# evalboard_v2_9.net
KiCad netlist of a schematic drawn in EAGLE
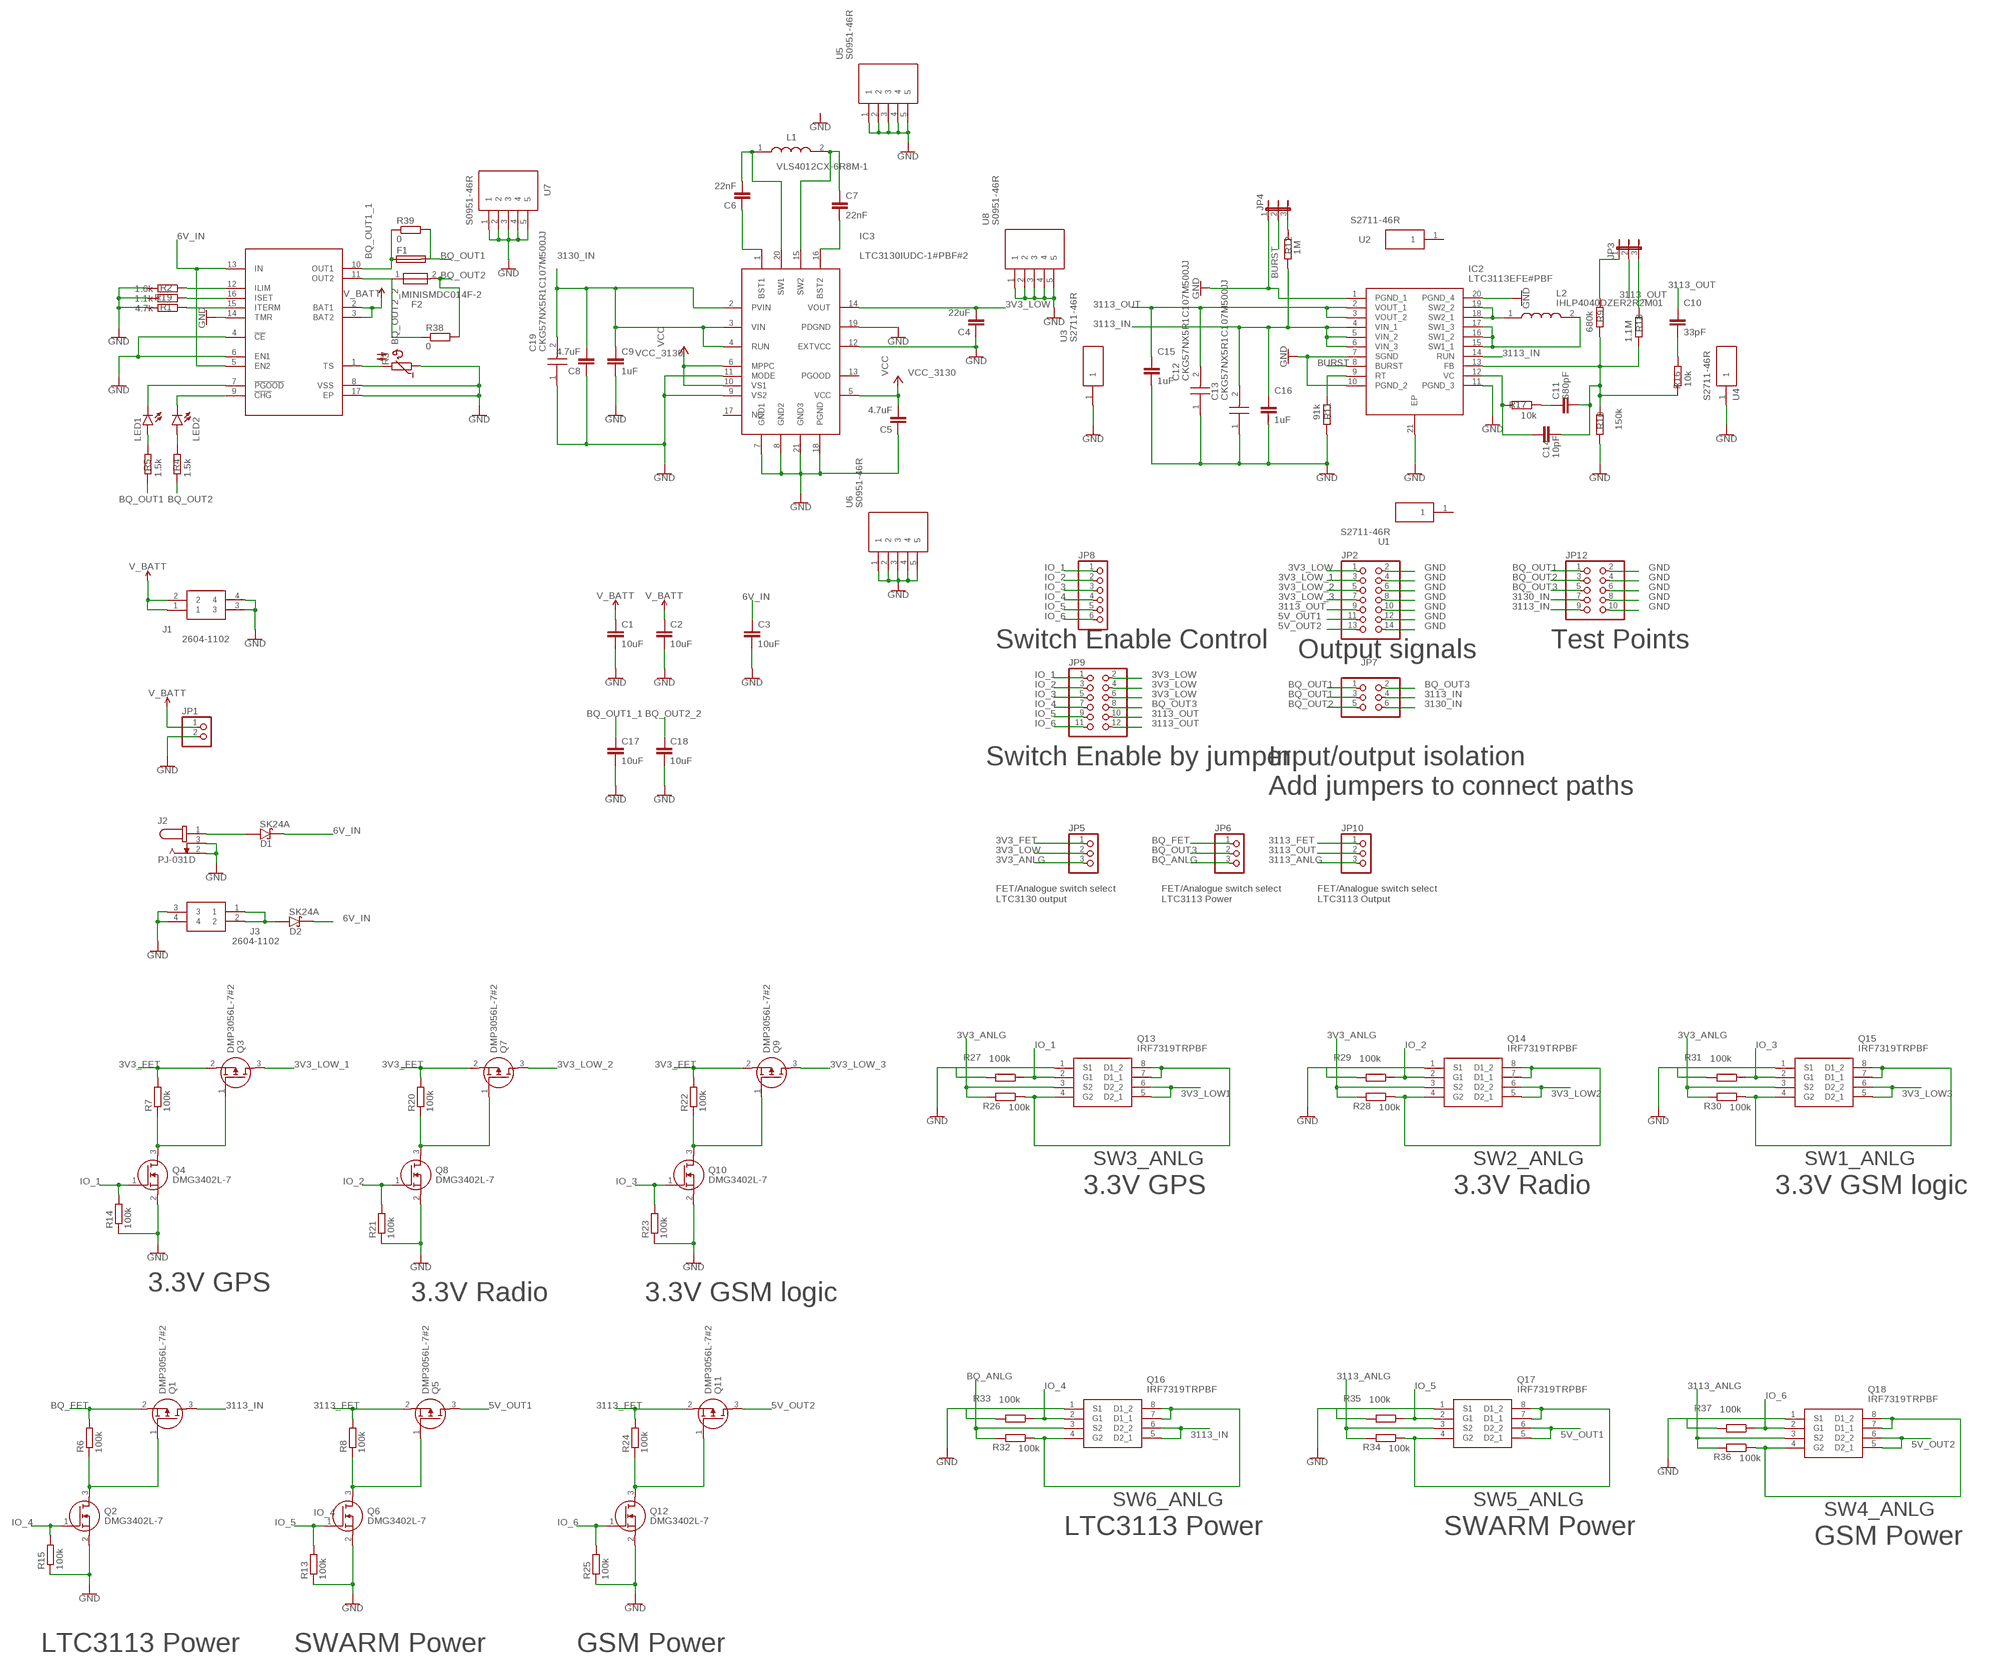
[diagram p0: schematic, sheet 1]

(export (version "E")
  (design (tool "Eeschema 10.0.6"))
  (components
    (comp (ref "C1")
      (value "10uF")
      (footprint "eagle-import:C1210")
      (libsource (lib "eagle-import") (part "C-EUC1210"))
    )
    (comp (ref "C2")
      (value "10uF")
      (footprint "eagle-import:C1210")
      (libsource (lib "eagle-import") (part "C-EUC1210"))
    )
    (comp (ref "C3")
      (value "10uF")
      (footprint "eagle-import:C1210")
      (libsource (lib "eagle-import") (part "C-EUC1210"))
    )
    (comp (ref "C4")
      (value "22uF")
      (footprint "eagle-import:C1210")
      (libsource (lib "eagle-import") (part "C-EUC1210"))
    )
    (comp (ref "C5")
      (value "4.7uF")
      (footprint "eagle-import:C1210")
      (libsource (lib "eagle-import") (part "C-EUC1210"))
    )
    (comp (ref "C6")
      (value "22nF")
      (footprint "eagle-import:C0603")
      (libsource (lib "eagle-import") (part "C-EUC0603"))
    )
    (comp (ref "C7")
      (value "22nF")
      (footprint "eagle-import:C0603")
      (libsource (lib "eagle-import") (part "C-EUC0603"))
    )
    (comp (ref "C8")
      (value "4.7uF")
      (footprint "eagle-import:C1210")
      (libsource (lib "eagle-import") (part "C-EUC1210"))
    )
    (comp (ref "C9")
      (value "1uF")
      (footprint "eagle-import:C0603")
      (libsource (lib "eagle-import") (part "C-EUC0603"))
    )
    (comp (ref "C10")
      (value "33pF")
      (footprint "eagle-import:C0603")
      (libsource (lib "eagle-import") (part "C-EUC0603"))
    )
    (comp (ref "C11")
      (value "680pF")
      (footprint "eagle-import:C0603")
      (libsource (lib "eagle-import") (part "C-EUC0603"))
    )
    (comp (ref "C12")
      (value "CKG57NX5R1C107M500JJ")
      (footprint "eagle-import:CAPC6050X550N")
      (fields (field (name "MOUSER_PART_NUMBER") "810-CKG57NX5R1C107MJ"))
      (libsource (lib "eagle-import") (part "CKG57NX5R1C107M500JJ"))
    )
    (comp (ref "C13")
      (value "CKG57NX5R1C107M500JJ")
      (footprint "eagle-import:CAPC6050X550N")
      (fields (field (name "MOUSER_PART_NUMBER") "810-CKG57NX5R1C107MJ"))
      (libsource (lib "eagle-import") (part "CKG57NX5R1C107M500JJ"))
    )
    (comp (ref "C14")
      (value "10pF")
      (footprint "eagle-import:C0603")
      (libsource (lib "eagle-import") (part "C-EUC0603"))
    )
    (comp (ref "C15")
      (value "1uF")
      (footprint "eagle-import:C0603")
      (libsource (lib "eagle-import") (part "C-EUC0603"))
    )
    (comp (ref "C16")
      (value "1uF")
      (footprint "eagle-import:C0603")
      (libsource (lib "eagle-import") (part "C-EUC0603"))
    )
    (comp (ref "C17")
      (value "10uF")
      (footprint "eagle-import:C1210")
      (libsource (lib "eagle-import") (part "C-EUC1210"))
    )
    (comp (ref "C18")
      (value "10uF")
      (footprint "eagle-import:C1210")
      (libsource (lib "eagle-import") (part "C-EUC1210"))
    )
    (comp (ref "C19")
      (value "CKG57NX5R1C107M500JJ")
      (footprint "eagle-import:CAPC6050X550N")
      (fields (field (name "MOUSER_PART_NUMBER") "810-CKG57NX5R1C107MJ"))
      (libsource (lib "eagle-import") (part "CKG57NX5R1C107M500JJ"))
    )
    (comp (ref "D1")
      (value "SK24A")
      (footprint "eagle-import:DIOM4325X250N")
      (fields (field (name "DIGI-KEY_PART_NUMBER") "1655-SK24ATR-ND") (field (name "MF") "SMC Diode"))
      (libsource (lib "eagle-import") (part "SK24A"))
    )
    (comp (ref "D2")
      (value "SK24A")
      (footprint "eagle-import:DIOM4325X250N")
      (fields (field (name "DIGI-KEY_PART_NUMBER") "1655-SK24ATR-ND") (field (name "MF") "SMC Diode"))
      (libsource (lib "eagle-import") (part "SK24A"))
    )
    (comp (ref "F1")
      (value "MF-USHT150KX-2SMD")
      (footprint "eagle-import:1210")
      (libsource (lib "eagle-import") (part "MF-USHT150KX-2SMD"))
    )
    (comp (ref "F2")
      (value "MINISMDC014F-2")
      (footprint "eagle-import:FUSSC455X324X89-2N")
      (fields (field (name "MF") "Littelfuse Inc."))
      (libsource (lib "eagle-import") (part "MINISMDC014F-2"))
    )
    (comp (ref "IC1")
      (value "BQ24074")
      (footprint "eagle-import:QFN50P300X300X100-17N")
      (libsource (lib "eagle-import") (part "BQ24074"))
    )
    (comp (ref "IC2")
      (value "LTC3113EFE#PBF")
      (footprint "eagle-import:SOP65P640X120-21N")
      (fields (field (name "MOUSER_PART_NUMBER") "584-LTC3113EFE#PBF"))
      (libsource (lib "eagle-import") (part "LTC3113EFE#PBF"))
    )
    (comp (ref "IC3")
      (value "LTC3130IUDC-1#PBF#2")
      (footprint "eagle-import:QFN50P300X400X80-21N")
      (fields (field (name "MANUFACTURER_PART_NUMBER") "LTC3130IUDC-1#PBF"))
      (libsource (lib "eagle-import") (part "LTC3130IUDC-1#PBF#2"))
    )
    (comp (ref "J1")
      (value "2604-1102")
      (footprint "eagle-import:26041102")
      (libsource (lib "eagle-import") (part "2604-1102"))
    )
    (comp (ref "J2")
      (value "PJ-031D")
      (footprint "eagle-import:CUI_PJ-031D")
      (fields (field (name "MF") "CUI Devices"))
      (libsource (lib "eagle-import") (part "PJ-031D"))
    )
    (comp (ref "J3")
      (value "2604-1102")
      (footprint "eagle-import:26041102")
      (libsource (lib "eagle-import") (part "2604-1102"))
    )
    (comp (ref "JP1")
      (value "PINHD-1X2")
      (footprint "eagle-import:1X02")
      (libsource (lib "eagle-import") (part "PINHD-1X2"))
    )
    (comp (ref "JP2")
      (value "PINHD-2X7")
      (footprint "eagle-import:2X07")
      (libsource (lib "eagle-import") (part "PINHD-2X7"))
    )
    (comp (ref "JP3")
      (value "JP2E")
      (footprint "eagle-import:JP2")
      (libsource (lib "eagle-import") (part "JP2E"))
    )
    (comp (ref "JP4")
      (value "JP2E")
      (footprint "eagle-import:JP2")
      (libsource (lib "eagle-import") (part "JP2E"))
    )
    (comp (ref "JP5")
      (value "PINHD-1X3")
      (footprint "eagle-import:1X03")
      (libsource (lib "eagle-import") (part "PINHD-1X3"))
    )
    (comp (ref "JP6")
      (value "PINHD-1X3")
      (footprint "eagle-import:1X03")
      (libsource (lib "eagle-import") (part "PINHD-1X3"))
    )
    (comp (ref "JP7")
      (value "PINHD-2X3")
      (footprint "eagle-import:2X03")
      (libsource (lib "eagle-import") (part "PINHD-2X3"))
    )
    (comp (ref "JP8")
      (value "PINHD-1X6")
      (footprint "eagle-import:1X06")
      (libsource (lib "eagle-import") (part "PINHD-1X6"))
    )
    (comp (ref "JP9")
      (value "PINHD-2X6")
      (footprint "eagle-import:2X06")
      (libsource (lib "eagle-import") (part "PINHD-2X6"))
    )
    (comp (ref "JP10")
      (value "PINHD-1X3")
      (footprint "eagle-import:1X03")
      (libsource (lib "eagle-import") (part "PINHD-1X3"))
    )
    (comp (ref "JP12")
      (value "PINHD-2X5")
      (footprint "eagle-import:2X05")
      (libsource (lib "eagle-import") (part "PINHD-2X5"))
    )
    (comp (ref "L1")
      (value "VLS4012CX-6R8M-1")
      (footprint "eagle-import:VLS4012")
      (libsource (lib "eagle-import") (part "VLS4012CX-6R8M-1"))
    )
    (comp (ref "L2")
      (value "IHLP4040DZER2R2M01")
      (footprint "eagle-import:INDPM108102X400N")
      (fields (field (name "MOUSER_PART_NUMBER") "70-IHLP4040DZER2R2M0"))
      (libsource (lib "eagle-import") (part "IHLP4040DZER2R2M01"))
    )
    (comp (ref "LED1")
      (value "LEDCHIP-LED0603")
      (footprint "eagle-import:CHIP-LED0603")
      (libsource (lib "eagle-import") (part "LEDCHIP-LED0603"))
    )
    (comp (ref "LED2")
      (value "LEDCHIP-LED0603")
      (footprint "eagle-import:CHIP-LED0603")
      (libsource (lib "eagle-import") (part "LEDCHIP-LED0603"))
    )
    (comp (ref "Q1")
      (value "DMP3056L-7#2")
      (footprint "eagle-import:SOT96P240X100-3N")
      (fields
        (field (name "ARROW_PART_NUMBER") "DMP3056L-7")
        (field (name "MOUSER_PART_NUMBER") "621-DMP3056L-7")
      )
      (libsource (lib "eagle-import") (part "DMP3056L-7#2"))
    )
    (comp (ref "Q2")
      (value "DMG3402L-7")
      (footprint "eagle-import:SOT96P240X110-3N")
      (fields (field (name "MOUSER_PART_NUMBER") "621-DMG3402L-7"))
      (libsource (lib "eagle-import") (part "DMG3402L-7"))
    )
    (comp (ref "Q3")
      (value "DMP3056L-7#2")
      (footprint "eagle-import:SOT96P240X100-3N")
      (fields
        (field (name "ARROW_PART_NUMBER") "DMP3056L-7")
        (field (name "MOUSER_PART_NUMBER") "621-DMP3056L-7")
      )
      (libsource (lib "eagle-import") (part "DMP3056L-7#2"))
    )
    (comp (ref "Q4")
      (value "DMG3402L-7")
      (footprint "eagle-import:SOT96P240X110-3N")
      (fields (field (name "MOUSER_PART_NUMBER") "621-DMG3402L-7"))
      (libsource (lib "eagle-import") (part "DMG3402L-7"))
    )
    (comp (ref "Q5")
      (value "DMP3056L-7#2")
      (footprint "eagle-import:SOT96P240X100-3N")
      (fields
        (field (name "ARROW_PART_NUMBER") "DMP3056L-7")
        (field (name "MOUSER_PART_NUMBER") "621-DMP3056L-7")
      )
      (libsource (lib "eagle-import") (part "DMP3056L-7#2"))
    )
    (comp (ref "Q6")
      (value "DMG3402L-7")
      (footprint "eagle-import:SOT96P240X110-3N")
      (fields (field (name "MOUSER_PART_NUMBER") "621-DMG3402L-7"))
      (libsource (lib "eagle-import") (part "DMG3402L-7"))
    )
    (comp (ref "Q7")
      (value "DMP3056L-7#2")
      (footprint "eagle-import:SOT96P240X100-3N")
      (fields
        (field (name "ARROW_PART_NUMBER") "DMP3056L-7")
        (field (name "MOUSER_PART_NUMBER") "621-DMP3056L-7")
      )
      (libsource (lib "eagle-import") (part "DMP3056L-7#2"))
    )
    (comp (ref "Q8")
      (value "DMG3402L-7")
      (footprint "eagle-import:SOT96P240X110-3N")
      (fields (field (name "MOUSER_PART_NUMBER") "621-DMG3402L-7"))
      (libsource (lib "eagle-import") (part "DMG3402L-7"))
    )
    (comp (ref "Q9")
      (value "DMP3056L-7#2")
      (footprint "eagle-import:SOT96P240X100-3N")
      (fields
        (field (name "ARROW_PART_NUMBER") "DMP3056L-7")
        (field (name "MOUSER_PART_NUMBER") "621-DMP3056L-7")
      )
      (libsource (lib "eagle-import") (part "DMP3056L-7#2"))
    )
    (comp (ref "Q10")
      (value "DMG3402L-7")
      (footprint "eagle-import:SOT96P240X110-3N")
      (fields (field (name "MOUSER_PART_NUMBER") "621-DMG3402L-7"))
      (libsource (lib "eagle-import") (part "DMG3402L-7"))
    )
    (comp (ref "Q11")
      (value "DMP3056L-7#2")
      (footprint "eagle-import:SOT96P240X100-3N")
      (fields
        (field (name "ARROW_PART_NUMBER") "DMP3056L-7")
        (field (name "MOUSER_PART_NUMBER") "621-DMP3056L-7")
      )
      (libsource (lib "eagle-import") (part "DMP3056L-7#2"))
    )
    (comp (ref "Q12")
      (value "DMG3402L-7")
      (footprint "eagle-import:SOT96P240X110-3N")
      (fields (field (name "MOUSER_PART_NUMBER") "621-DMG3402L-7"))
      (libsource (lib "eagle-import") (part "DMG3402L-7"))
    )
    (comp (ref "Q13")
      (value "IRF7319TRPBF")
      (footprint "eagle-import:SOIC127P600X175-8N")
      (fields (field (name "MOUSER_PART_NUMBER") "942-IRF7319TRPBF"))
      (libsource (lib "eagle-import") (part "IRF7319TRPBF"))
    )
    (comp (ref "Q14")
      (value "IRF7319TRPBF")
      (footprint "eagle-import:SOIC127P600X175-8N")
      (fields (field (name "MOUSER_PART_NUMBER") "942-IRF7319TRPBF"))
      (libsource (lib "eagle-import") (part "IRF7319TRPBF"))
    )
    (comp (ref "Q15")
      (value "IRF7319TRPBF")
      (footprint "eagle-import:SOIC127P600X175-8N")
      (fields (field (name "MOUSER_PART_NUMBER") "942-IRF7319TRPBF"))
      (libsource (lib "eagle-import") (part "IRF7319TRPBF"))
    )
    (comp (ref "Q16")
      (value "IRF7319TRPBF")
      (footprint "eagle-import:SOIC127P600X175-8N")
      (fields (field (name "MOUSER_PART_NUMBER") "942-IRF7319TRPBF"))
      (libsource (lib "eagle-import") (part "IRF7319TRPBF"))
    )
    (comp (ref "Q17")
      (value "IRF7319TRPBF")
      (footprint "eagle-import:SOIC127P600X175-8N")
      (fields (field (name "MOUSER_PART_NUMBER") "942-IRF7319TRPBF"))
      (libsource (lib "eagle-import") (part "IRF7319TRPBF"))
    )
    (comp (ref "Q18")
      (value "IRF7319TRPBF")
      (footprint "eagle-import:SOIC127P600X175-8N")
      (fields (field (name "MOUSER_PART_NUMBER") "942-IRF7319TRPBF"))
      (libsource (lib "eagle-import") (part "IRF7319TRPBF"))
    )
    (comp (ref "R1")
      (value "4.7k")
      (footprint "eagle-import:R0603")
      (libsource (lib "eagle-import") (part "R-EU_R0603"))
    )
    (comp (ref "R2")
      (value "1.6k")
      (footprint "eagle-import:R0603")
      (libsource (lib "eagle-import") (part "R-EU_R0603"))
    )
    (comp (ref "R3")
      (value "10k")
      (footprint "eagle-import:P640")
      (libsource (lib "eagle-import") (part "NTC640"))
    )
    (comp (ref "R4")
      (value "1.5k")
      (footprint "eagle-import:R0603")
      (libsource (lib "eagle-import") (part "R-EU_R0603"))
    )
    (comp (ref "R5")
      (value "1.5k")
      (footprint "eagle-import:R0603")
      (libsource (lib "eagle-import") (part "R-EU_R0603"))
    )
    (comp (ref "R6")
      (value "100k")
      (footprint "eagle-import:R0603")
      (libsource (lib "eagle-import") (part "R-EU_R0603"))
    )
    (comp (ref "R7")
      (value "100k")
      (footprint "eagle-import:R0603")
      (libsource (lib "eagle-import") (part "R-EU_R0603"))
    )
    (comp (ref "R8")
      (value "100k")
      (footprint "eagle-import:R0603")
      (libsource (lib "eagle-import") (part "R-EU_R0603"))
    )
    (comp (ref "R9")
      (value "680k")
      (footprint "eagle-import:R0603")
      (libsource (lib "eagle-import") (part "R-EU_R0603"))
    )
    (comp (ref "R10")
      (value "150k")
      (footprint "eagle-import:R0603")
      (libsource (lib "eagle-import") (part "R-EU_R0603"))
    )
    (comp (ref "R11")
      (value "91k")
      (footprint "eagle-import:R0603")
      (libsource (lib "eagle-import") (part "R-EU_R0603"))
    )
    (comp (ref "R12")
      (value "1M")
      (footprint "eagle-import:R0603")
      (libsource (lib "eagle-import") (part "R-EU_R0603"))
    )
    (comp (ref "R13")
      (value "100k")
      (footprint "eagle-import:R0603")
      (libsource (lib "eagle-import") (part "R-EU_R0603"))
    )
    (comp (ref "R14")
      (value "100k")
      (footprint "eagle-import:R0603")
      (libsource (lib "eagle-import") (part "R-EU_R0603"))
    )
    (comp (ref "R15")
      (value "100k")
      (footprint "eagle-import:R0603")
      (libsource (lib "eagle-import") (part "R-EU_R0603"))
    )
    (comp (ref "R16")
      (value "10k")
      (footprint "eagle-import:R0603")
      (libsource (lib "eagle-import") (part "R-EU_R0603"))
    )
    (comp (ref "R17")
      (value "10k")
      (footprint "eagle-import:R0603")
      (libsource (lib "eagle-import") (part "R-EU_R0603"))
    )
    (comp (ref "R18")
      (value "1.1M")
      (footprint "eagle-import:R0603")
      (libsource (lib "eagle-import") (part "R-EU_R0603"))
    )
    (comp (ref "R19")
      (value "1.1k")
      (footprint "eagle-import:R0603")
      (libsource (lib "eagle-import") (part "R-EU_R0603"))
    )
    (comp (ref "R20")
      (value "100k")
      (footprint "eagle-import:R0603")
      (libsource (lib "eagle-import") (part "R-EU_R0603"))
    )
    (comp (ref "R21")
      (value "100k")
      (footprint "eagle-import:R0603")
      (libsource (lib "eagle-import") (part "R-EU_R0603"))
    )
    (comp (ref "R22")
      (value "100k")
      (footprint "eagle-import:R0603")
      (libsource (lib "eagle-import") (part "R-EU_R0603"))
    )
    (comp (ref "R23")
      (value "100k")
      (footprint "eagle-import:R0603")
      (libsource (lib "eagle-import") (part "R-EU_R0603"))
    )
    (comp (ref "R24")
      (value "100k")
      (footprint "eagle-import:R0603")
      (libsource (lib "eagle-import") (part "R-EU_R0603"))
    )
    (comp (ref "R25")
      (value "100k")
      (footprint "eagle-import:R0603")
      (libsource (lib "eagle-import") (part "R-EU_R0603"))
    )
    (comp (ref "R26")
      (value "100k")
      (footprint "eagle-import:R0603")
      (libsource (lib "eagle-import") (part "R-EU_R0603"))
    )
    (comp (ref "R27")
      (value "100k")
      (footprint "eagle-import:R0603")
      (libsource (lib "eagle-import") (part "R-EU_R0603"))
    )
    (comp (ref "R28")
      (value "100k")
      (footprint "eagle-import:R0603")
      (libsource (lib "eagle-import") (part "R-EU_R0603"))
    )
    (comp (ref "R29")
      (value "100k")
      (footprint "eagle-import:R0603")
      (libsource (lib "eagle-import") (part "R-EU_R0603"))
    )
    (comp (ref "R30")
      (value "100k")
      (footprint "eagle-import:R0603")
      (libsource (lib "eagle-import") (part "R-EU_R0603"))
    )
    (comp (ref "R31")
      (value "100k")
      (footprint "eagle-import:R0603")
      (libsource (lib "eagle-import") (part "R-EU_R0603"))
    )
    (comp (ref "R32")
      (value "100k")
      (footprint "eagle-import:R0603")
      (libsource (lib "eagle-import") (part "R-EU_R0603"))
    )
    (comp (ref "R33")
      (value "100k")
      (footprint "eagle-import:R0603")
      (libsource (lib "eagle-import") (part "R-EU_R0603"))
    )
    (comp (ref "R34")
      (value "100k")
      (footprint "eagle-import:R0603")
      (libsource (lib "eagle-import") (part "R-EU_R0603"))
    )
    (comp (ref "R35")
      (value "100k")
      (footprint "eagle-import:R0603")
      (libsource (lib "eagle-import") (part "R-EU_R0603"))
    )
    (comp (ref "R36")
      (value "100k")
      (footprint "eagle-import:R0603")
      (libsource (lib "eagle-import") (part "R-EU_R0603"))
    )
    (comp (ref "R37")
      (value "100k")
      (footprint "eagle-import:R0603")
      (libsource (lib "eagle-import") (part "R-EU_R0603"))
    )
    (comp (ref "R38")
      (value "0")
      (footprint "eagle-import:R0603")
      (libsource (lib "eagle-import") (part "R-EU_R0603"))
    )
    (comp (ref "R39")
      (value "0")
      (footprint "eagle-import:R0603")
      (libsource (lib "eagle-import") (part "R-EU_R0603"))
    )
    (comp (ref "U1")
      (value "S2711-46R")
      (footprint "eagle-import:S271146R")
      (libsource (lib "eagle-import") (part "S2711-46R"))
    )
    (comp (ref "U2")
      (value "S2711-46R")
      (footprint "eagle-import:S271146R")
      (libsource (lib "eagle-import") (part "S2711-46R"))
    )
    (comp (ref "U3")
      (value "S2711-46R")
      (footprint "eagle-import:S271146R")
      (libsource (lib "eagle-import") (part "S2711-46R"))
    )
    (comp (ref "U4")
      (value "S2711-46R")
      (footprint "eagle-import:S271146R")
      (libsource (lib "eagle-import") (part "S2711-46R"))
    )
    (comp (ref "U5")
      (value "S0951-46R")
      (footprint "eagle-import:S095146R")
      (fields (field (name "MOUSER_PART_NUMBER") "855-S0951-46R"))
      (libsource (lib "eagle-import") (part "S0951-46R"))
    )
    (comp (ref "U6")
      (value "S0951-46R")
      (footprint "eagle-import:S095146R")
      (fields (field (name "MOUSER_PART_NUMBER") "855-S0951-46R"))
      (libsource (lib "eagle-import") (part "S0951-46R"))
    )
    (comp (ref "U7")
      (value "S0951-46R")
      (footprint "eagle-import:S095146R")
      (fields (field (name "MOUSER_PART_NUMBER") "855-S0951-46R"))
      (libsource (lib "eagle-import") (part "S0951-46R"))
    )
    (comp (ref "U8")
      (value "S0951-46R")
      (footprint "eagle-import:S095146R")
      (fields (field (name "MOUSER_PART_NUMBER") "855-S0951-46R"))
      (libsource (lib "eagle-import") (part "S0951-46R"))
    )
  )
  (nets
    (net (code "1") (name "/3V3_ANLG") (class "Default")
      (node (ref "JP5") (pin "3") (pinfunction "3_3") (pintype "passive"))
      (node (ref "Q13") (pin "3") (pinfunction "S2_3") (pintype "bidirectional"))
      (node (ref "Q14") (pin "3") (pinfunction "S2_3") (pintype "bidirectional"))
      (node (ref "Q15") (pin "3") (pinfunction "S2_3") (pintype "bidirectional"))
      (node (ref "R26") (pin "2") (pinfunction "2_2") (pintype "passive"))
      (node (ref "R28") (pin "2") (pinfunction "2_2") (pintype "passive"))
      (node (ref "R30") (pin "2") (pinfunction "2_2") (pintype "passive"))
    )
    (net (code "2") (name "/3V3_FET") (class "Default")
      (node (ref "JP5") (pin "1") (pinfunction "1_1") (pintype "passive"))
      (node (ref "Q3") (pin "2") (pinfunction "S_2") (pintype "bidirectional"))
      (node (ref "Q7") (pin "2") (pinfunction "S_2") (pintype "bidirectional"))
      (node (ref "Q9") (pin "2") (pinfunction "S_2") (pintype "bidirectional"))
      (node (ref "R20") (pin "2") (pinfunction "2_2") (pintype "passive"))
      (node (ref "R22") (pin "2") (pinfunction "2_2") (pintype "passive"))
      (node (ref "R7") (pin "2") (pinfunction "2_2") (pintype "passive"))
    )
    (net (code "3") (name "/3V3_LOW") (class "Default")
      (node (ref "C4") (pin "2") (pinfunction "2_2") (pintype "passive"))
      (node (ref "IC3") (pin "14") (pinfunction "VOUT_14") (pintype "output"))
      (node (ref "JP2") (pin "1") (pinfunction "1_1") (pintype "passive"))
      (node (ref "JP5") (pin "2") (pinfunction "2_2") (pintype "passive"))
      (node (ref "JP9") (pin "2") (pinfunction "2_2") (pintype "passive"))
      (node (ref "JP9") (pin "4") (pinfunction "4_4") (pintype "passive"))
      (node (ref "JP9") (pin "6") (pinfunction "6_6") (pintype "passive"))
    )
    (net (code "4") (name "/3V3_LOW1") (class "Default")
      (node (ref "Q13") (pin "5") (pinfunction "D2_1_5") (pintype "bidirectional"))
      (node (ref "Q13") (pin "6") (pinfunction "D2_2_6") (pintype "bidirectional"))
    )
    (net (code "5") (name "/3V3_LOW2") (class "Default")
      (node (ref "Q14") (pin "5") (pinfunction "D2_1_5") (pintype "bidirectional"))
      (node (ref "Q14") (pin "6") (pinfunction "D2_2_6") (pintype "bidirectional"))
    )
    (net (code "6") (name "/3V3_LOW3") (class "Default")
      (node (ref "Q15") (pin "5") (pinfunction "D2_1_5") (pintype "bidirectional"))
      (node (ref "Q15") (pin "6") (pinfunction "D2_2_6") (pintype "bidirectional"))
    )
    (net (code "7") (name "/3V3_LOW_1") (class "Default")
      (node (ref "JP2") (pin "3") (pinfunction "3_3") (pintype "passive"))
      (node (ref "Q3") (pin "3") (pinfunction "D_3") (pintype "bidirectional"))
    )
    (net (code "8") (name "/3V3_LOW_2") (class "Default")
      (node (ref "JP2") (pin "5") (pinfunction "5_5") (pintype "passive"))
      (node (ref "Q7") (pin "3") (pinfunction "D_3") (pintype "bidirectional"))
    )
    (net (code "9") (name "/3V3_LOW_3") (class "Default")
      (node (ref "JP2") (pin "7") (pinfunction "7_7") (pintype "passive"))
      (node (ref "Q9") (pin "3") (pinfunction "D_3") (pintype "bidirectional"))
    )
    (net (code "10") (name "/5V_OUT1") (class "Default")
      (node (ref "JP2") (pin "11") (pinfunction "11_11") (pintype "passive"))
      (node (ref "Q17") (pin "5") (pinfunction "D2_1_5") (pintype "bidirectional"))
      (node (ref "Q17") (pin "6") (pinfunction "D2_2_6") (pintype "bidirectional"))
      (node (ref "Q5") (pin "3") (pinfunction "D_3") (pintype "bidirectional"))
    )
    (net (code "11") (name "/5V_OUT2") (class "Default")
      (node (ref "JP2") (pin "13") (pinfunction "13_13") (pintype "passive"))
      (node (ref "Q11") (pin "3") (pinfunction "D_3") (pintype "bidirectional"))
      (node (ref "Q18") (pin "5") (pinfunction "D2_1_5") (pintype "bidirectional"))
      (node (ref "Q18") (pin "6") (pinfunction "D2_2_6") (pintype "bidirectional"))
    )
    (net (code "12") (name "/6V_IN") (class "Default")
      (node (ref "C3") (pin "1") (pinfunction "1_1") (pintype "passive"))
      (node (ref "D1") (pin "C") (pinfunction "K_C") (pintype "passive"))
      (node (ref "D2") (pin "C") (pinfunction "K_C") (pintype "passive"))
      (node (ref "IC1") (pin "13") (pinfunction "IN_13") (pintype "bidirectional"))
      (node (ref "IC1") (pin "5") (pinfunction "EN2_5") (pintype "bidirectional"))
    )
    (net (code "13") (name "/3113_ANLG") (class "Default")
      (node (ref "JP10") (pin "3") (pinfunction "3_3") (pintype "passive"))
      (node (ref "Q17") (pin "3") (pinfunction "S2_3") (pintype "bidirectional"))
      (node (ref "Q18") (pin "3") (pinfunction "S2_3") (pintype "bidirectional"))
      (node (ref "R34") (pin "2") (pinfunction "2_2") (pintype "passive"))
      (node (ref "R36") (pin "2") (pinfunction "2_2") (pintype "passive"))
    )
    (net (code "14") (name "/3113_FET") (class "Default")
      (node (ref "JP10") (pin "1") (pinfunction "1_1") (pintype "passive"))
      (node (ref "Q11") (pin "2") (pinfunction "S_2") (pintype "bidirectional"))
      (node (ref "Q5") (pin "2") (pinfunction "S_2") (pintype "bidirectional"))
      (node (ref "R24") (pin "2") (pinfunction "2_2") (pintype "passive"))
      (node (ref "R8") (pin "2") (pinfunction "2_2") (pintype "passive"))
    )
    (net (code "15") (name "/3113_IN") (class "Default")
      (node (ref "C13") (pin "2") (pinfunction "2_2") (pintype "bidirectional"))
      (node (ref "C16") (pin "1") (pinfunction "1_1") (pintype "passive"))
      (node (ref "IC2") (pin "14") (pinfunction "RUN_14") (pintype "bidirectional"))
      (node (ref "IC2") (pin "4") (pinfunction "VIN_1_4") (pintype "bidirectional"))
      (node (ref "IC2") (pin "5") (pinfunction "VIN_2_5") (pintype "bidirectional"))
      (node (ref "IC2") (pin "6") (pinfunction "VIN_3_6") (pintype "bidirectional"))
      (node (ref "JP12") (pin "9") (pinfunction "9_9") (pintype "passive"))
      (node (ref "JP7") (pin "4") (pinfunction "4_4") (pintype "passive"))
      (node (ref "Q1") (pin "3") (pinfunction "D_3") (pintype "bidirectional"))
      (node (ref "Q16") (pin "5") (pinfunction "D2_1_5") (pintype "bidirectional"))
      (node (ref "Q16") (pin "6") (pinfunction "D2_2_6") (pintype "bidirectional"))
      (node (ref "R12") (pin "1") (pinfunction "1_1") (pintype "passive"))
    )
    (net (code "16") (name "/3113_OUT") (class "Default")
      (node (ref "C10") (pin "1") (pinfunction "1_1") (pintype "passive"))
      (node (ref "C12") (pin "2") (pinfunction "2_2") (pintype "bidirectional"))
      (node (ref "C15") (pin "1") (pinfunction "1_1") (pintype "passive"))
      (node (ref "IC2") (pin "2") (pinfunction "VOUT_1_2") (pintype "bidirectional"))
      (node (ref "IC2") (pin "3") (pinfunction "VOUT_2_3") (pintype "bidirectional"))
      (node (ref "JP10") (pin "2") (pinfunction "2_2") (pintype "passive"))
      (node (ref "JP2") (pin "9") (pinfunction "9_9") (pintype "passive"))
      (node (ref "JP3") (pin "2") (pinfunction "2_2") (pintype "passive"))
      (node (ref "JP9") (pin "10") (pinfunction "10_10") (pintype "passive"))
      (node (ref "JP9") (pin "12") (pinfunction "12_12") (pintype "passive"))
    )
    (net (code "17") (name "/3130_IN") (class "Default")
      (node (ref "C19") (pin "2") (pinfunction "2_2") (pintype "bidirectional"))
      (node (ref "C8") (pin "2") (pinfunction "2_2") (pintype "passive"))
      (node (ref "C9") (pin "1") (pinfunction "1_1") (pintype "passive"))
      (node (ref "IC3") (pin "2") (pinfunction "PVIN_2") (pintype "input"))
      (node (ref "IC3") (pin "3") (pinfunction "VIN_3") (pintype "input"))
      (node (ref "IC3") (pin "4") (pinfunction "RUN_4") (pintype "bidirectional"))
      (node (ref "JP12") (pin "7") (pinfunction "7_7") (pintype "passive"))
      (node (ref "JP7") (pin "6") (pinfunction "6_6") (pintype "passive"))
    )
    (net (code "18") (name "/BQ_ANLG") (class "Default")
      (node (ref "JP6") (pin "3") (pinfunction "3_3") (pintype "passive"))
      (node (ref "Q16") (pin "3") (pinfunction "S2_3") (pintype "bidirectional"))
      (node (ref "R32") (pin "2") (pinfunction "2_2") (pintype "passive"))
    )
    (net (code "19") (name "/BQ_FET") (class "Default")
      (node (ref "JP6") (pin "1") (pinfunction "1_1") (pintype "passive"))
      (node (ref "Q1") (pin "2") (pinfunction "S_2") (pintype "bidirectional"))
      (node (ref "R6") (pin "2") (pinfunction "2_2") (pintype "passive"))
    )
    (net (code "20") (name "/BQ_OUT1") (class "Default")
      (node (ref "F1") (pin "2") (pinfunction "2_2") (pintype "passive"))
      (node (ref "JP12") (pin "1") (pinfunction "1_1") (pintype "passive"))
      (node (ref "JP7") (pin "1") (pinfunction "1_1") (pintype "passive"))
      (node (ref "JP7") (pin "3") (pinfunction "3_3") (pintype "passive"))
      (node (ref "R39") (pin "2") (pinfunction "2_2") (pintype "passive"))
      (node (ref "R5") (pin "2") (pinfunction "2_2") (pintype "passive"))
    )
    (net (code "21") (name "/BQ_OUT1_1") (class "Default")
      (node (ref "C17") (pin "1") (pinfunction "1_1") (pintype "passive"))
      (node (ref "F1") (pin "1") (pinfunction "1_1") (pintype "passive"))
      (node (ref "IC1") (pin "10") (pinfunction "OUT1_10") (pintype "bidirectional"))
      (node (ref "R39") (pin "1") (pinfunction "1_1") (pintype "passive"))
    )
    (net (code "22") (name "/BQ_OUT2") (class "Default")
      (node (ref "F2") (pin "2") (pinfunction "2_2") (pintype "passive"))
      (node (ref "JP12") (pin "3") (pinfunction "3_3") (pintype "passive"))
      (node (ref "JP7") (pin "5") (pinfunction "5_5") (pintype "passive"))
      (node (ref "R38") (pin "2") (pinfunction "2_2") (pintype "passive"))
      (node (ref "R4") (pin "2") (pinfunction "2_2") (pintype "passive"))
    )
    (net (code "23") (name "/BQ_OUT2_2") (class "Default")
      (node (ref "C18") (pin "1") (pinfunction "1_1") (pintype "passive"))
      (node (ref "F2") (pin "1") (pinfunction "1_1") (pintype "passive"))
      (node (ref "IC1") (pin "11") (pinfunction "OUT2_11") (pintype "bidirectional"))
      (node (ref "R38") (pin "1") (pinfunction "1_1") (pintype "passive"))
    )
    (net (code "24") (name "/BQ_OUT3") (class "Default")
      (node (ref "JP12") (pin "5") (pinfunction "5_5") (pintype "passive"))
      (node (ref "JP6") (pin "2") (pinfunction "2_2") (pintype "passive"))
      (node (ref "JP7") (pin "2") (pinfunction "2_2") (pintype "passive"))
      (node (ref "JP9") (pin "8") (pinfunction "8_8") (pintype "passive"))
    )
    (net (code "25") (name "/BURST") (class "Default")
      (node (ref "IC2") (pin "8") (pinfunction "BURST_8") (pintype "bidirectional"))
      (node (ref "JP4") (pin "2") (pinfunction "2_2") (pintype "passive"))
    )
    (net (code "26") (name "/IO_1") (class "Default")
      (node (ref "JP8") (pin "1") (pinfunction "1_1") (pintype "passive"))
      (node (ref "JP9") (pin "1") (pinfunction "1_1") (pintype "passive"))
      (node (ref "Q13") (pin "2") (pinfunction "G1_2") (pintype "bidirectional"))
      (node (ref "Q4") (pin "1") (pinfunction "G_1") (pintype "bidirectional"))
      (node (ref "R14") (pin "2") (pinfunction "2_2") (pintype "passive"))
      (node (ref "R27") (pin "1") (pinfunction "1_1") (pintype "passive"))
      (node (ref "R27") (pin "2") (pinfunction "2_2") (pintype "passive"))
      (node (ref "R29") (pin "2") (pinfunction "2_2") (pintype "passive"))
      (node (ref "R31") (pin "2") (pinfunction "2_2") (pintype "passive"))
      (node (ref "R33") (pin "2") (pinfunction "2_2") (pintype "passive"))
      (node (ref "R35") (pin "2") (pinfunction "2_2") (pintype "passive"))
      (node (ref "R37") (pin "2") (pinfunction "2_2") (pintype "passive"))
    )
    (net (code "27") (name "/IO_2") (class "Default")
      (node (ref "JP8") (pin "2") (pinfunction "2_2") (pintype "passive"))
      (node (ref "JP9") (pin "3") (pinfunction "3_3") (pintype "passive"))
      (node (ref "Q14") (pin "2") (pinfunction "G1_2") (pintype "bidirectional"))
      (node (ref "Q8") (pin "1") (pinfunction "G_1") (pintype "bidirectional"))
      (node (ref "R21") (pin "2") (pinfunction "2_2") (pintype "passive"))
      (node (ref "R29") (pin "1") (pinfunction "1_1") (pintype "passive"))
    )
    (net (code "28") (name "/IO_3") (class "Default")
      (node (ref "JP8") (pin "3") (pinfunction "3_3") (pintype "passive"))
      (node (ref "JP9") (pin "5") (pinfunction "5_5") (pintype "passive"))
      (node (ref "Q10") (pin "1") (pinfunction "G_1") (pintype "bidirectional"))
      (node (ref "Q15") (pin "2") (pinfunction "G1_2") (pintype "bidirectional"))
      (node (ref "R23") (pin "2") (pinfunction "2_2") (pintype "passive"))
      (node (ref "R31") (pin "1") (pinfunction "1_1") (pintype "passive"))
    )
    (net (code "29") (name "/IO_4") (class "Default")
      (node (ref "JP8") (pin "4") (pinfunction "4_4") (pintype "passive"))
      (node (ref "JP9") (pin "7") (pinfunction "7_7") (pintype "passive"))
      (node (ref "Q16") (pin "2") (pinfunction "G1_2") (pintype "bidirectional"))
      (node (ref "Q2") (pin "1") (pinfunction "G_1") (pintype "bidirectional"))
      (node (ref "R15") (pin "2") (pinfunction "2_2") (pintype "passive"))
      (node (ref "R33") (pin "1") (pinfunction "1_1") (pintype "passive"))
    )
    (net (code "30") (name "/IO_5") (class "Default")
      (node (ref "JP8") (pin "5") (pinfunction "5_5") (pintype "passive"))
      (node (ref "JP9") (pin "9") (pinfunction "9_9") (pintype "passive"))
      (node (ref "Q17") (pin "2") (pinfunction "G1_2") (pintype "bidirectional"))
      (node (ref "Q6") (pin "1") (pinfunction "G_1") (pintype "bidirectional"))
      (node (ref "R13") (pin "2") (pinfunction "2_2") (pintype "passive"))
      (node (ref "R35") (pin "1") (pinfunction "1_1") (pintype "passive"))
    )
    (net (code "31") (name "/IO_6") (class "Default")
      (node (ref "JP8") (pin "6") (pinfunction "6_6") (pintype "passive"))
      (node (ref "JP9") (pin "11") (pinfunction "11_11") (pintype "passive"))
      (node (ref "Q12") (pin "1") (pinfunction "G_1") (pintype "bidirectional"))
      (node (ref "Q18") (pin "2") (pinfunction "G1_2") (pintype "bidirectional"))
      (node (ref "R25") (pin "2") (pinfunction "2_2") (pintype "passive"))
      (node (ref "R37") (pin "1") (pinfunction "1_1") (pintype "passive"))
    )
    (net (code "32") (name "GND") (class "Default")
      (node (ref "C1") (pin "2") (pinfunction "2_2") (pintype "passive"))
      (node (ref "C12") (pin "1") (pinfunction "1_1") (pintype "bidirectional"))
      (node (ref "C13") (pin "1") (pinfunction "1_1") (pintype "bidirectional"))
      (node (ref "C15") (pin "2") (pinfunction "2_2") (pintype "passive"))
      (node (ref "C16") (pin "2") (pinfunction "2_2") (pintype "passive"))
      (node (ref "C17") (pin "2") (pinfunction "2_2") (pintype "passive"))
      (node (ref "C18") (pin "2") (pinfunction "2_2") (pintype "passive"))
      (node (ref "C19") (pin "1") (pinfunction "1_1") (pintype "bidirectional"))
      (node (ref "C2") (pin "2") (pinfunction "2_2") (pintype "passive"))
      (node (ref "C3") (pin "2") (pinfunction "2_2") (pintype "passive"))
      (node (ref "C4") (pin "1") (pinfunction "1_1") (pintype "passive"))
      (node (ref "C5") (pin "1") (pinfunction "1_1") (pintype "passive"))
      (node (ref "C8") (pin "1") (pinfunction "1_1") (pintype "passive"))
      (node (ref "C9") (pin "2") (pinfunction "2_2") (pintype "passive"))
      (node (ref "IC1") (pin "14") (pinfunction "TMR_14") (pintype "bidirectional"))
      (node (ref "IC1") (pin "17") (pinfunction "EP_17") (pintype "bidirectional"))
      (node (ref "IC1") (pin "4") (pinfunction "~{CE}_4") (pintype "bidirectional"))
      (node (ref "IC1") (pin "6") (pinfunction "EN1_6") (pintype "bidirectional"))
      (node (ref "IC1") (pin "8") (pinfunction "VSS_8") (pintype "bidirectional"))
      (node (ref "IC2") (pin "1") (pinfunction "PGND_1_1") (pintype "bidirectional"))
      (node (ref "IC2") (pin "10") (pinfunction "PGND_2_10") (pintype "bidirectional"))
      (node (ref "IC2") (pin "11") (pinfunction "PGND_3_11") (pintype "bidirectional"))
      (node (ref "IC2") (pin "20") (pinfunction "PGND_4_20") (pintype "bidirectional"))
      (node (ref "IC2") (pin "21") (pinfunction "EP_21") (pintype "bidirectional"))
      (node (ref "IC2") (pin "7") (pinfunction "SGND_7") (pintype "bidirectional"))
      (node (ref "IC3") (pin "11") (pinfunction "MODE_11") (pintype "bidirectional"))
      (node (ref "IC3") (pin "12") (pinfunction "EXTVCC_12") (pintype "bidirectional"))
      (node (ref "IC3") (pin "18") (pinfunction "PGND_18") (pintype "bidirectional"))
      (node (ref "IC3") (pin "19") (pinfunction "PDGND_19") (pintype "bidirectional"))
      (node (ref "IC3") (pin "21") (pinfunction "GND3_21") (pintype "bidirectional"))
      (node (ref "IC3") (pin "7") (pinfunction "GND1_7") (pintype "bidirectional"))
      (node (ref "IC3") (pin "8") (pinfunction "GND2_8") (pintype "bidirectional"))
      (node (ref "IC3") (pin "9") (pinfunction "VS2_9") (pintype "bidirectional"))
      (node (ref "J1") (pin "3") (pinfunction "3_3") (pintype "bidirectional"))
      (node (ref "J1") (pin "4") (pinfunction "4_4") (pintype "bidirectional"))
      (node (ref "J2") (pin "2") (pinfunction "2_2") (pintype "passive"))
      (node (ref "J2") (pin "3") (pinfunction "3_3") (pintype "passive"))
      (node (ref "J3") (pin "3") (pinfunction "3_3") (pintype "bidirectional"))
      (node (ref "J3") (pin "4") (pinfunction "4_4") (pintype "bidirectional"))
      (node (ref "JP1") (pin "2") (pinfunction "2_2") (pintype "passive"))
      (node (ref "JP12") (pin "10") (pinfunction "10_10") (pintype "passive"))
      (node (ref "JP12") (pin "2") (pinfunction "2_2") (pintype "passive"))
      (node (ref "JP12") (pin "4") (pinfunction "4_4") (pintype "passive"))
      (node (ref "JP12") (pin "6") (pinfunction "6_6") (pintype "passive"))
      (node (ref "JP12") (pin "8") (pinfunction "8_8") (pintype "passive"))
      (node (ref "JP2") (pin "10") (pinfunction "10_10") (pintype "passive"))
      (node (ref "JP2") (pin "12") (pinfunction "12_12") (pintype "passive"))
      (node (ref "JP2") (pin "14") (pinfunction "14_14") (pintype "passive"))
      (node (ref "JP2") (pin "2") (pinfunction "2_2") (pintype "passive"))
      (node (ref "JP2") (pin "4") (pinfunction "4_4") (pintype "passive"))
      (node (ref "JP2") (pin "6") (pinfunction "6_6") (pintype "passive"))
      (node (ref "JP2") (pin "8") (pinfunction "8_8") (pintype "passive"))
      (node (ref "JP4") (pin "1") (pinfunction "1_1") (pintype "passive"))
      (node (ref "Q10") (pin "2") (pinfunction "S_2") (pintype "bidirectional"))
      (node (ref "Q12") (pin "2") (pinfunction "S_2") (pintype "bidirectional"))
      (node (ref "Q13") (pin "1") (pinfunction "S1_1") (pintype "bidirectional"))
      (node (ref "Q14") (pin "1") (pinfunction "S1_1") (pintype "bidirectional"))
      (node (ref "Q15") (pin "1") (pinfunction "S1_1") (pintype "bidirectional"))
      (node (ref "Q16") (pin "1") (pinfunction "S1_1") (pintype "bidirectional"))
      (node (ref "Q17") (pin "1") (pinfunction "S1_1") (pintype "bidirectional"))
      (node (ref "Q18") (pin "1") (pinfunction "S1_1") (pintype "bidirectional"))
      (node (ref "Q2") (pin "2") (pinfunction "S_2") (pintype "bidirectional"))
      (node (ref "Q4") (pin "2") (pinfunction "S_2") (pintype "bidirectional"))
      (node (ref "Q6") (pin "2") (pinfunction "S_2") (pintype "bidirectional"))
      (node (ref "Q8") (pin "2") (pinfunction "S_2") (pintype "bidirectional"))
      (node (ref "R1") (pin "2") (pinfunction "2_2") (pintype "passive"))
      (node (ref "R10") (pin "1") (pinfunction "1_1") (pintype "passive"))
      (node (ref "R11") (pin "1") (pinfunction "1_1") (pintype "passive"))
      (node (ref "R13") (pin "1") (pinfunction "1_1") (pintype "passive"))
      (node (ref "R14") (pin "1") (pinfunction "1_1") (pintype "passive"))
      (node (ref "R15") (pin "1") (pinfunction "1_1") (pintype "passive"))
      (node (ref "R19") (pin "2") (pinfunction "2_2") (pintype "passive"))
      (node (ref "R2") (pin "2") (pinfunction "2_2") (pintype "passive"))
      (node (ref "R21") (pin "1") (pinfunction "1_1") (pintype "passive"))
      (node (ref "R23") (pin "1") (pinfunction "1_1") (pintype "passive"))
      (node (ref "R25") (pin "1") (pinfunction "1_1") (pintype "passive"))
      (node (ref "R3") (pin "1") (pinfunction "1_1") (pintype "passive"))
      (node (ref "U3") (pin "1") (pinfunction "1_1") (pintype "bidirectional"))
      (node (ref "U4") (pin "1") (pinfunction "1_1") (pintype "bidirectional"))
      (node (ref "U5") (pin "1") (pinfunction "1_1") (pintype "bidirectional"))
      (node (ref "U5") (pin "2") (pinfunction "2_2") (pintype "bidirectional"))
      (node (ref "U5") (pin "3") (pinfunction "3_3") (pintype "bidirectional"))
      (node (ref "U5") (pin "4") (pinfunction "4_4") (pintype "bidirectional"))
      (node (ref "U5") (pin "5") (pinfunction "5_5") (pintype "bidirectional"))
      (node (ref "U6") (pin "1") (pinfunction "1_1") (pintype "bidirectional"))
      (node (ref "U6") (pin "2") (pinfunction "2_2") (pintype "bidirectional"))
      (node (ref "U6") (pin "3") (pinfunction "3_3") (pintype "bidirectional"))
      (node (ref "U6") (pin "4") (pinfunction "4_4") (pintype "bidirectional"))
      (node (ref "U6") (pin "5") (pinfunction "5_5") (pintype "bidirectional"))
      (node (ref "U7") (pin "1") (pinfunction "1_1") (pintype "bidirectional"))
      (node (ref "U7") (pin "2") (pinfunction "2_2") (pintype "bidirectional"))
      (node (ref "U7") (pin "3") (pinfunction "3_3") (pintype "bidirectional"))
      (node (ref "U7") (pin "4") (pinfunction "4_4") (pintype "bidirectional"))
      (node (ref "U7") (pin "5") (pinfunction "5_5") (pintype "bidirectional"))
      (node (ref "U8") (pin "1") (pinfunction "1_1") (pintype "bidirectional"))
      (node (ref "U8") (pin "2") (pinfunction "2_2") (pintype "bidirectional"))
      (node (ref "U8") (pin "3") (pinfunction "3_3") (pintype "bidirectional"))
      (node (ref "U8") (pin "4") (pinfunction "4_4") (pintype "bidirectional"))
      (node (ref "U8") (pin "5") (pinfunction "5_5") (pintype "bidirectional"))
    )
    (net (code "33") (name "Net-(C10-Pad2)") (class "Default")
      (node (ref "C10") (pin "2") (pinfunction "2_2") (pintype "passive"))
      (node (ref "R16") (pin "1") (pinfunction "1_1") (pintype "passive"))
    )
    (net (code "34") (name "Net-(C11-Pad1)") (class "Default")
      (node (ref "C11") (pin "1") (pinfunction "1_1") (pintype "passive"))
      (node (ref "R17") (pin "1") (pinfunction "1_1") (pintype "passive"))
    )
    (net (code "35") (name "Net-(D1-PadA)") (class "Default")
      (node (ref "D1") (pin "A") (pinfunction "A_A") (pintype "passive"))
      (node (ref "J2") (pin "1") (pinfunction "1_1") (pintype "passive"))
    )
    (net (code "36") (name "Net-(D2-PadA)") (class "Default")
      (node (ref "D2") (pin "A") (pinfunction "A_A") (pintype "passive"))
      (node (ref "J3") (pin "1") (pinfunction "1_1") (pintype "bidirectional"))
      (node (ref "J3") (pin "2") (pinfunction "2_2") (pintype "bidirectional"))
    )
    (net (code "37") (name "Net-(IC1-ILIM)") (class "Default")
      (node (ref "IC1") (pin "12") (pinfunction "ILIM_12") (pintype "bidirectional"))
      (node (ref "R2") (pin "1") (pinfunction "1_1") (pintype "passive"))
    )
    (net (code "38") (name "Net-(IC1-ISET)") (class "Default")
      (node (ref "IC1") (pin "16") (pinfunction "ISET_16") (pintype "bidirectional"))
      (node (ref "R19") (pin "1") (pinfunction "1_1") (pintype "passive"))
    )
    (net (code "39") (name "Net-(IC1-ITERM)") (class "Default")
      (node (ref "IC1") (pin "15") (pinfunction "ITERM_15") (pintype "bidirectional"))
      (node (ref "R1") (pin "1") (pinfunction "1_1") (pintype "passive"))
    )
    (net (code "40") (name "Net-(IC1-TS)") (class "Default")
      (node (ref "IC1") (pin "1") (pinfunction "TS_1") (pintype "bidirectional"))
      (node (ref "R3") (pin "2") (pinfunction "2_2") (pintype "passive"))
    )
    (net (code "41") (name "Net-(IC1-~{CHG})") (class "Default")
      (node (ref "IC1") (pin "9") (pinfunction "~{CHG}_9") (pintype "bidirectional"))
      (node (ref "LED2") (pin "C") (pinfunction "C_C") (pintype "passive"))
    )
    (net (code "42") (name "Net-(IC1-~{PGOOD})") (class "Default")
      (node (ref "IC1") (pin "7") (pinfunction "~{PGOOD}_7") (pintype "bidirectional"))
      (node (ref "LED1") (pin "C") (pinfunction "C_C") (pintype "passive"))
    )
    (net (code "43") (name "Net-(IC2-FB)") (class "Default")
      (node (ref "C11") (pin "2") (pinfunction "2_2") (pintype "passive"))
      (node (ref "C14") (pin "2") (pinfunction "2_2") (pintype "passive"))
      (node (ref "IC2") (pin "13") (pinfunction "FB_13") (pintype "bidirectional"))
      (node (ref "R10") (pin "2") (pinfunction "2_2") (pintype "passive"))
      (node (ref "R16") (pin "2") (pinfunction "2_2") (pintype "passive"))
      (node (ref "R18") (pin "1") (pinfunction "1_1") (pintype "passive"))
      (node (ref "R9") (pin "1") (pinfunction "1_1") (pintype "passive"))
    )
    (net (code "44") (name "Net-(IC2-RT)") (class "Default")
      (node (ref "IC2") (pin "9") (pinfunction "RT_9") (pintype "bidirectional"))
      (node (ref "R11") (pin "2") (pinfunction "2_2") (pintype "passive"))
    )
    (net (code "45") (name "Net-(IC2-SW1_1)") (class "Default")
      (node (ref "IC2") (pin "15") (pinfunction "SW1_1_15") (pintype "bidirectional"))
      (node (ref "IC2") (pin "16") (pinfunction "SW1_2_16") (pintype "bidirectional"))
      (node (ref "IC2") (pin "17") (pinfunction "SW1_3_17") (pintype "bidirectional"))
      (node (ref "L2") (pin "2") (pinfunction "2_2") (pintype "bidirectional"))
    )
    (net (code "46") (name "Net-(IC2-SW2_1)") (class "Default")
      (node (ref "IC2") (pin "18") (pinfunction "SW2_1_18") (pintype "bidirectional"))
      (node (ref "IC2") (pin "19") (pinfunction "SW2_2_19") (pintype "bidirectional"))
      (node (ref "L2") (pin "1") (pinfunction "1_1") (pintype "bidirectional"))
    )
    (net (code "47") (name "Net-(IC2-VC)") (class "Default")
      (node (ref "C14") (pin "1") (pinfunction "1_1") (pintype "passive"))
      (node (ref "IC2") (pin "12") (pinfunction "VC_12") (pintype "bidirectional"))
      (node (ref "R17") (pin "2") (pinfunction "2_2") (pintype "passive"))
    )
    (net (code "48") (name "Net-(IC3-BST1)") (class "Default")
      (node (ref "C6") (pin "1") (pinfunction "1_1") (pintype "passive"))
      (node (ref "IC3") (pin "1") (pinfunction "BST1_1") (pintype "bidirectional"))
    )
    (net (code "49") (name "Net-(IC3-BST2)") (class "Default")
      (node (ref "C7") (pin "2") (pinfunction "2_2") (pintype "passive"))
      (node (ref "IC3") (pin "16") (pinfunction "BST2_16") (pintype "bidirectional"))
    )
    (net (code "50") (name "Net-(IC3-SW1)") (class "Default")
      (node (ref "C6") (pin "2") (pinfunction "2_2") (pintype "passive"))
      (node (ref "IC3") (pin "20") (pinfunction "SW1_20") (pintype "bidirectional"))
      (node (ref "L1") (pin "1") (pinfunction "1_1") (pintype "bidirectional"))
    )
    (net (code "51") (name "Net-(IC3-SW2)") (class "Default")
      (node (ref "C7") (pin "1") (pinfunction "1_1") (pintype "passive"))
      (node (ref "IC3") (pin "15") (pinfunction "SW2_15") (pintype "bidirectional"))
      (node (ref "L1") (pin "2") (pinfunction "2_2") (pintype "bidirectional"))
    )
    (net (code "52") (name "Net-(JP3-Pad1)") (class "Default")
      (node (ref "JP3") (pin "1") (pinfunction "1_1") (pintype "passive"))
      (node (ref "R9") (pin "2") (pinfunction "2_2") (pintype "passive"))
    )
    (net (code "53") (name "Net-(JP3-Pad3)") (class "Default")
      (node (ref "JP3") (pin "3") (pinfunction "3_3") (pintype "passive"))
      (node (ref "R18") (pin "2") (pinfunction "2_2") (pintype "passive"))
    )
    (net (code "54") (name "Net-(JP4-Pad3)") (class "Default")
      (node (ref "JP4") (pin "3") (pinfunction "3_3") (pintype "passive"))
      (node (ref "R12") (pin "2") (pinfunction "2_2") (pintype "passive"))
    )
    (net (code "55") (name "Net-(LED1-PadA)") (class "Default")
      (node (ref "LED1") (pin "A") (pinfunction "A_A") (pintype "passive"))
      (node (ref "R5") (pin "1") (pinfunction "1_1") (pintype "passive"))
    )
    (net (code "56") (name "Net-(LED2-PadA)") (class "Default")
      (node (ref "LED2") (pin "A") (pinfunction "A_A") (pintype "passive"))
      (node (ref "R4") (pin "1") (pinfunction "1_1") (pintype "passive"))
    )
    (net (code "57") (name "Net-(Q1-G)") (class "Default")
      (node (ref "Q1") (pin "1") (pinfunction "G_1") (pintype "bidirectional"))
      (node (ref "Q2") (pin "3") (pinfunction "D_3") (pintype "bidirectional"))
      (node (ref "R6") (pin "1") (pinfunction "1_1") (pintype "passive"))
    )
    (net (code "58") (name "Net-(Q3-G)") (class "Default")
      (node (ref "Q3") (pin "1") (pinfunction "G_1") (pintype "bidirectional"))
      (node (ref "Q4") (pin "3") (pinfunction "D_3") (pintype "bidirectional"))
      (node (ref "R7") (pin "1") (pinfunction "1_1") (pintype "passive"))
    )
    (net (code "59") (name "Net-(Q5-G)") (class "Default")
      (node (ref "Q5") (pin "1") (pinfunction "G_1") (pintype "bidirectional"))
      (node (ref "Q6") (pin "3") (pinfunction "D_3") (pintype "bidirectional"))
      (node (ref "R8") (pin "1") (pinfunction "1_1") (pintype "passive"))
    )
    (net (code "60") (name "Net-(Q7-G)") (class "Default")
      (node (ref "Q7") (pin "1") (pinfunction "G_1") (pintype "bidirectional"))
      (node (ref "Q8") (pin "3") (pinfunction "D_3") (pintype "bidirectional"))
      (node (ref "R20") (pin "1") (pinfunction "1_1") (pintype "passive"))
    )
    (net (code "61") (name "Net-(Q10-D)") (class "Default")
      (node (ref "Q10") (pin "3") (pinfunction "D_3") (pintype "bidirectional"))
      (node (ref "Q9") (pin "1") (pinfunction "G_1") (pintype "bidirectional"))
      (node (ref "R22") (pin "1") (pinfunction "1_1") (pintype "passive"))
    )
    (net (code "62") (name "Net-(Q11-G)") (class "Default")
      (node (ref "Q11") (pin "1") (pinfunction "G_1") (pintype "bidirectional"))
      (node (ref "Q12") (pin "3") (pinfunction "D_3") (pintype "bidirectional"))
      (node (ref "R24") (pin "1") (pinfunction "1_1") (pintype "passive"))
    )
    (net (code "63") (name "Net-(Q13-D1_1)") (class "Default")
      (node (ref "Q13") (pin "4") (pinfunction "G2_4") (pintype "bidirectional"))
      (node (ref "Q13") (pin "7") (pinfunction "D1_1_7") (pintype "bidirectional"))
      (node (ref "Q13") (pin "8") (pinfunction "D1_2_8") (pintype "bidirectional"))
      (node (ref "R26") (pin "1") (pinfunction "1_1") (pintype "passive"))
    )
    (net (code "64") (name "Net-(Q14-D1_1)") (class "Default")
      (node (ref "Q14") (pin "4") (pinfunction "G2_4") (pintype "bidirectional"))
      (node (ref "Q14") (pin "7") (pinfunction "D1_1_7") (pintype "bidirectional"))
      (node (ref "Q14") (pin "8") (pinfunction "D1_2_8") (pintype "bidirectional"))
      (node (ref "R28") (pin "1") (pinfunction "1_1") (pintype "passive"))
    )
    (net (code "65") (name "Net-(Q15-D1_1)") (class "Default")
      (node (ref "Q15") (pin "4") (pinfunction "G2_4") (pintype "bidirectional"))
      (node (ref "Q15") (pin "7") (pinfunction "D1_1_7") (pintype "bidirectional"))
      (node (ref "Q15") (pin "8") (pinfunction "D1_2_8") (pintype "bidirectional"))
      (node (ref "R30") (pin "1") (pinfunction "1_1") (pintype "passive"))
    )
    (net (code "66") (name "Net-(Q16-D1_1)") (class "Default")
      (node (ref "Q16") (pin "4") (pinfunction "G2_4") (pintype "bidirectional"))
      (node (ref "Q16") (pin "7") (pinfunction "D1_1_7") (pintype "bidirectional"))
      (node (ref "Q16") (pin "8") (pinfunction "D1_2_8") (pintype "bidirectional"))
      (node (ref "R32") (pin "1") (pinfunction "1_1") (pintype "passive"))
    )
    (net (code "67") (name "Net-(Q17-D1_1)") (class "Default")
      (node (ref "Q17") (pin "4") (pinfunction "G2_4") (pintype "bidirectional"))
      (node (ref "Q17") (pin "7") (pinfunction "D1_1_7") (pintype "bidirectional"))
      (node (ref "Q17") (pin "8") (pinfunction "D1_2_8") (pintype "bidirectional"))
      (node (ref "R34") (pin "1") (pinfunction "1_1") (pintype "passive"))
    )
    (net (code "68") (name "Net-(Q18-D1_1)") (class "Default")
      (node (ref "Q18") (pin "4") (pinfunction "G2_4") (pintype "bidirectional"))
      (node (ref "Q18") (pin "7") (pinfunction "D1_1_7") (pintype "bidirectional"))
      (node (ref "Q18") (pin "8") (pinfunction "D1_2_8") (pintype "bidirectional"))
      (node (ref "R36") (pin "1") (pinfunction "1_1") (pintype "passive"))
    )
    (net (code "69") (name "VCC") (class "Default")
      (node (ref "C5") (pin "2") (pinfunction "2_2") (pintype "passive"))
      (node (ref "IC3") (pin "10") (pinfunction "VS1_10") (pintype "bidirectional"))
      (node (ref "IC3") (pin "5") (pinfunction "VCC_5") (pintype "bidirectional"))
      (node (ref "IC3") (pin "6") (pinfunction "MPPC_6") (pintype "bidirectional"))
    )
    (net (code "70") (name "V_BATT") (class "Default")
      (node (ref "C1") (pin "1") (pinfunction "1_1") (pintype "passive"))
      (node (ref "C2") (pin "1") (pinfunction "1_1") (pintype "passive"))
      (node (ref "IC1") (pin "2") (pinfunction "BAT1_2") (pintype "bidirectional"))
      (node (ref "IC1") (pin "3") (pinfunction "BAT2_3") (pintype "bidirectional"))
      (node (ref "J1") (pin "1") (pinfunction "1_1") (pintype "bidirectional"))
      (node (ref "J1") (pin "2") (pinfunction "2_2") (pintype "bidirectional"))
      (node (ref "JP1") (pin "1") (pinfunction "1_1") (pintype "passive"))
    )
    (net (code "71") (name "unconnected-(IC3-NC-Pad17)") (class "Default")
      (node (ref "IC3") (pin "17") (pinfunction "NC_17") (pintype "bidirectional"))
    )
    (net (code "72") (name "unconnected-(IC3-PGOOD-Pad13)") (class "Default")
      (node (ref "IC3") (pin "13") (pinfunction "PGOOD_13") (pintype "bidirectional"))
    )
    (net (code "73") (name "unconnected-(U1-Pad1)") (class "Default")
      (node (ref "U1") (pin "1") (pinfunction "1_1") (pintype "bidirectional"))
    )
    (net (code "74") (name "unconnected-(U2-Pad1)") (class "Default")
      (node (ref "U2") (pin "1") (pinfunction "1_1") (pintype "bidirectional"))
    )
  )
)
